# PiPicoInterface.net
KiCad netlist of a schematic drawn in Altium Designer
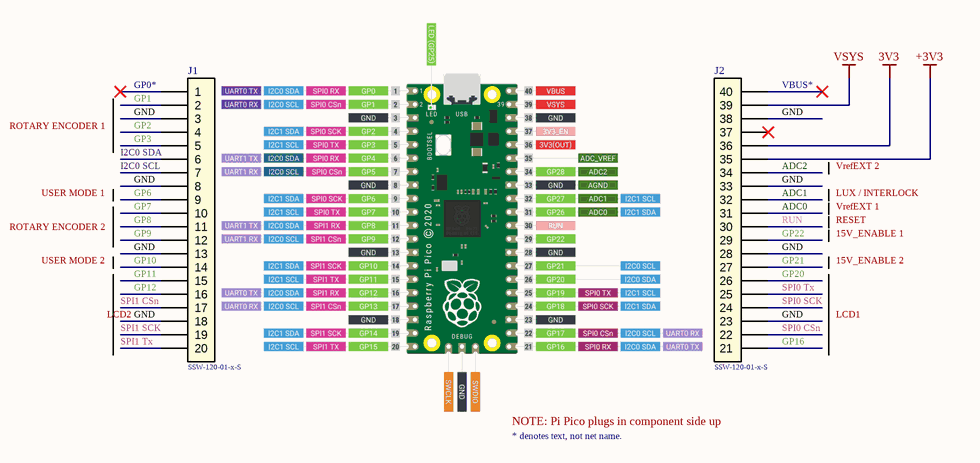
[diagram p0: PiPicoInterface.SchDoc]

(export (version "E")
  (design (tool "Eeschema 10.0.6"))
  (components
    (comp (ref "J1")
      (value "SSW-120-01-x-S")
      (footprint "SAMTEC_SSW-120-01-G-S")
      (description "Conn Socket Strip SKT 20 POS 2.54mm Solder ST Thru-Hole")
      (libsource (lib "Sainsbury Wellcome Centre") (part "Jack 20x1"))
    )
    (comp (ref "J2")
      (value "SSW-120-01-x-S - 21-40")
      (footprint "SAMTEC_SSW-120-01-G-S - 21-40")
      (description "Conn Socket Strip SKT 20 POS 2.54mm Solder ST Thru-Hole (pins 21 - 40)")
      (libsource (lib "Sainsbury Wellcome Centre") (part "Jack 20x1 21-40"))
    )
  )
  (nets
    (net (code "1") (name "+3V3") (class "Default")
      (node (ref "J2") (pin "35") (pinfunction "35_35") (pintype "passive"))
    )
    (net (code "2") (name "/ADC0") (class "Default")
      (node (ref "J2") (pin "31") (pinfunction "31_31") (pintype "passive"))
    )
    (net (code "3") (name "/ADC1") (class "Default")
      (node (ref "J2") (pin "32") (pinfunction "32_32") (pintype "passive"))
    )
    (net (code "4") (name "/ADC2") (class "Default")
      (node (ref "J2") (pin "34") (pinfunction "34_34") (pintype "passive"))
    )
    (net (code "5") (name "/GND") (class "Default")
      (node (ref "J1") (pin "13") (pinfunction "13_13") (pintype "passive"))
      (node (ref "J1") (pin "18") (pinfunction "18_18") (pintype "passive"))
      (node (ref "J1") (pin "3") (pinfunction "3_3") (pintype "passive"))
      (node (ref "J1") (pin "8") (pinfunction "8_8") (pintype "passive"))
      (node (ref "J2") (pin "23") (pinfunction "23_23") (pintype "passive"))
      (node (ref "J2") (pin "28") (pinfunction "28_28") (pintype "passive"))
      (node (ref "J2") (pin "33") (pinfunction "33_33") (pintype "passive"))
      (node (ref "J2") (pin "38") (pinfunction "38_38") (pintype "passive"))
    )
    (net (code "6") (name "/GP1") (class "Default")
      (node (ref "J1") (pin "2") (pinfunction "2_2") (pintype "passive"))
    )
    (net (code "7") (name "/GP2") (class "Default")
      (node (ref "J1") (pin "4") (pinfunction "4_4") (pintype "passive"))
    )
    (net (code "8") (name "/GP3") (class "Default")
      (node (ref "J1") (pin "5") (pinfunction "5_5") (pintype "passive"))
    )
    (net (code "9") (name "/GP6") (class "Default")
      (node (ref "J1") (pin "9") (pinfunction "9_9") (pintype "passive"))
    )
    (net (code "10") (name "/GP7") (class "Default")
      (node (ref "J1") (pin "10") (pinfunction "10_10") (pintype "passive"))
    )
    (net (code "11") (name "/GP8") (class "Default")
      (node (ref "J1") (pin "11") (pinfunction "11_11") (pintype "passive"))
    )
    (net (code "12") (name "/GP9") (class "Default")
      (node (ref "J1") (pin "12") (pinfunction "12_12") (pintype "passive"))
    )
    (net (code "13") (name "/GP10") (class "Default")
      (node (ref "J1") (pin "14") (pinfunction "14_14") (pintype "passive"))
    )
    (net (code "14") (name "/GP11") (class "Default")
      (node (ref "J1") (pin "15") (pinfunction "15_15") (pintype "passive"))
    )
    (net (code "15") (name "/GP12") (class "Default")
      (node (ref "J1") (pin "16") (pinfunction "16_16") (pintype "passive"))
    )
    (net (code "16") (name "/GP16") (class "Default")
      (node (ref "J2") (pin "21") (pinfunction "21_21") (pintype "passive"))
    )
    (net (code "17") (name "/GP20") (class "Default")
      (node (ref "J2") (pin "26") (pinfunction "26_26") (pintype "passive"))
    )
    (net (code "18") (name "/GP21") (class "Default")
      (node (ref "J2") (pin "27") (pinfunction "27_27") (pintype "passive"))
    )
    (net (code "19") (name "/GP22") (class "Default")
      (node (ref "J2") (pin "29") (pinfunction "29_29") (pintype "passive"))
    )
    (net (code "20") (name "/I2C0 SCL") (class "Default")
      (node (ref "J1") (pin "7") (pinfunction "7_7") (pintype "passive"))
    )
    (net (code "21") (name "/I2C0 SDA") (class "Default")
      (node (ref "J1") (pin "6") (pinfunction "6_6") (pintype "passive"))
    )
    (net (code "22") (name "/RUN") (class "Default")
      (node (ref "J2") (pin "30") (pinfunction "30_30") (pintype "passive"))
    )
    (net (code "23") (name "/SPI0 CSn") (class "Default")
      (node (ref "J2") (pin "22") (pinfunction "22_22") (pintype "passive"))
    )
    (net (code "24") (name "/SPI0 SCK") (class "Default")
      (node (ref "J2") (pin "24") (pinfunction "24_24") (pintype "passive"))
    )
    (net (code "25") (name "/SPI0 Tx") (class "Default")
      (node (ref "J2") (pin "25") (pinfunction "25_25") (pintype "passive"))
    )
    (net (code "26") (name "/SPI1 CSn") (class "Default")
      (node (ref "J1") (pin "17") (pinfunction "17_17") (pintype "passive"))
    )
    (net (code "27") (name "/SPI1 SCK") (class "Default")
      (node (ref "J1") (pin "19") (pinfunction "19_19") (pintype "passive"))
    )
    (net (code "28") (name "/SPI1 Tx") (class "Default")
      (node (ref "J1") (pin "20") (pinfunction "20_20") (pintype "passive"))
    )
    (net (code "29") (name "3V3") (class "Default")
      (node (ref "J2") (pin "36") (pinfunction "36_36") (pintype "passive"))
    )
    (net (code "30") (name "VSYS") (class "Default")
      (node (ref "J2") (pin "39") (pinfunction "39_39") (pintype "passive"))
    )
    (net (code "31") (name "unconnected-(J1-Pad1)") (class "Default")
      (node (ref "J1") (pin "1") (pinfunction "1_1") (pintype "passive+no_connect"))
    )
    (net (code "32") (name "unconnected-(J2-Pad37)") (class "Default")
      (node (ref "J2") (pin "37") (pinfunction "37_37") (pintype "passive+no_connect"))
    )
    (net (code "33") (name "unconnected-(J2-Pad40)") (class "Default")
      (node (ref "J2") (pin "40") (pinfunction "40_40") (pintype "passive+no_connect"))
    )
  )
)
